# RS232_M_V1.net
KiCad netlist of a schematic drawn in Altium Designer
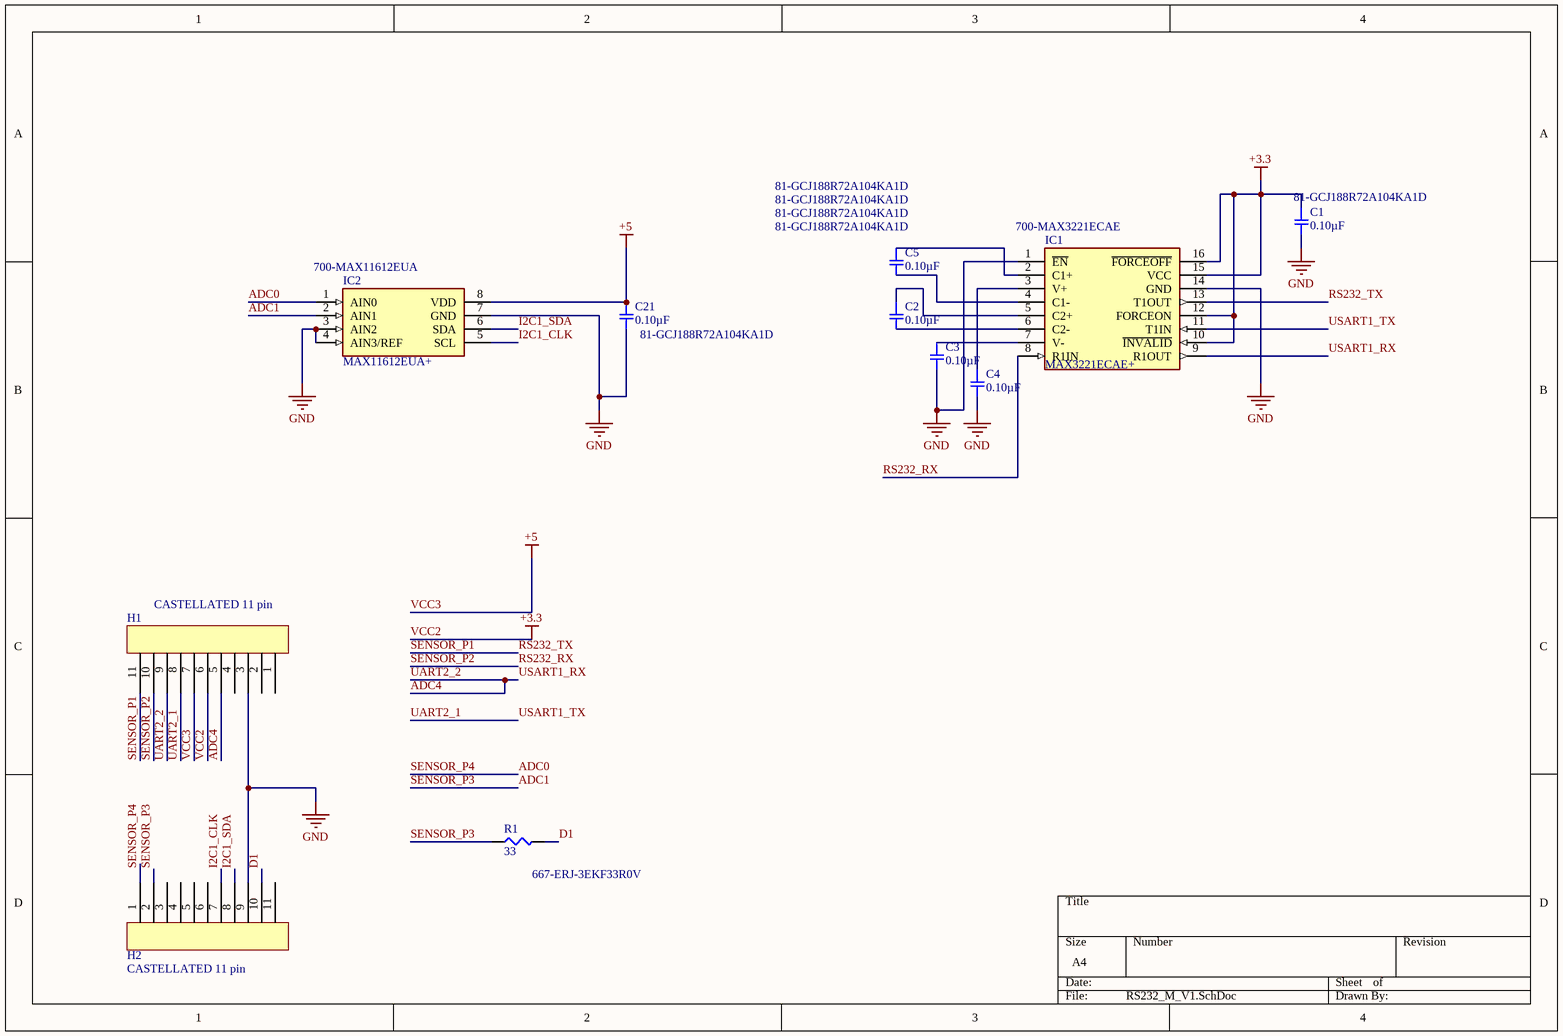
[diagram p0: RS232_M_V1.SchDoc]

(export (version "E")
  (design (tool "Eeschema 10.0.6"))
  (components
    (comp (ref "C1")
      (value "0.10µF")
      (footprint "SMD-0603C")
      (description "CAP CER 0.1UF 100V X7R 0603")
      (fields
        (field (name "PART NUMBER") "GCJ188R72A104KA01D")
        (field (name "DIGI-KEY PART NUMBER") "490-13420-1-ND")
        (field (name "SUPPLIER PART NUMBER 1") "81-GCJ188R72A104KA1D")
      )
      (libsource (lib "cap_murata") (part "CAPACITOR"))
    )
    (comp (ref "C2")
      (value "0.10µF")
      (footprint "SMD-0603C")
      (description "CAP CER 0.1UF 100V X7R 0603")
      (fields
        (field (name "PART NUMBER") "GCJ188R72A104KA01D")
        (field (name "DIGI-KEY PART NUMBER") "490-13420-1-ND")
        (field (name "SUPPLIER PART NUMBER 1") "81-GCJ188R72A104KA1D")
      )
      (libsource (lib "cap_murata") (part "CAPACITOR"))
    )
    (comp (ref "C3")
      (value "0.10µF")
      (footprint "SMD-0603C")
      (description "CAP CER 0.1UF 100V X7R 0603")
      (fields
        (field (name "PART NUMBER") "GCJ188R72A104KA01D")
        (field (name "DIGI-KEY PART NUMBER") "490-13420-1-ND")
        (field (name "SUPPLIER PART NUMBER 1") "81-GCJ188R72A104KA1D")
      )
      (libsource (lib "cap_murata") (part "CAPACITOR"))
    )
    (comp (ref "C4")
      (value "0.10µF")
      (footprint "SMD-0603C")
      (description "CAP CER 0.1UF 100V X7R 0603")
      (fields
        (field (name "PART NUMBER") "GCJ188R72A104KA01D")
        (field (name "DIGI-KEY PART NUMBER") "490-13420-1-ND")
        (field (name "SUPPLIER PART NUMBER 1") "81-GCJ188R72A104KA1D")
      )
      (libsource (lib "cap_murata") (part "CAPACITOR"))
    )
    (comp (ref "C5")
      (value "0.10µF")
      (footprint "SMD-0603C")
      (description "CAP CER 0.1UF 100V X7R 0603")
      (fields
        (field (name "PART NUMBER") "GCJ188R72A104KA01D")
        (field (name "DIGI-KEY PART NUMBER") "490-13420-1-ND")
        (field (name "SUPPLIER PART NUMBER 1") "81-GCJ188R72A104KA1D")
      )
      (libsource (lib "cap_murata") (part "CAPACITOR"))
    )
    (comp (ref "C21")
      (value "0.10µF")
      (footprint "SMD-0603C")
      (description "CAP CER 0.1UF 100V X7R 0603")
      (fields
        (field (name "PART NUMBER") "GCJ188R72A104KA01D")
        (field (name "DIGI-KEY PART NUMBER") "490-13420-1-ND")
        (field (name "SUPPLIER PART NUMBER 1") "81-GCJ188R72A104KA1D")
      )
      (libsource (lib "cap_murata") (part "CAPACITOR"))
    )
    (comp (ref "H1")
      (value "CASTELLATED 11 pin")
      (footprint "CASTELLATED 11 pin")
      (libsource (lib "USIB") (part "CASTELLATED 11 pin"))
    )
    (comp (ref "H2")
      (value "CASTELLATED 11 pin")
      (footprint "CASTELLATED 11 pin")
      (libsource (lib "") (part "CASTELLATED 11 pin_1"))
    )
    (comp (ref "IC1")
      (value "MAX3221ECAE+")
      (footprint "SamacSys:SOP65P778X199-16N")
      (description "Integrated Circuit")
      (fields (field (name "SUPPLIER PART NUMBER 1") "700-MAX3221ECAE"))
      (libsource (lib "*") (part "MAX3221ECAE+"))
    )
    (comp (ref "IC2")
      (value "MAX11612EUA+")
      (footprint "SOP65P490X110-8N")
      (description "Integrated Circuit")
      (fields (field (name "SUPPLIER PART NUMBER 1") "700-MAX11612EUA"))
      (libsource (lib "SamacSys") (part "MAX11612EUA+"))
    )
    (comp (ref "R1")
      (value "33")
      (footprint "SMD-0603-RES")
      (description "RES SMD 33 OHM 1% 1/10W 0603")
      (fields
        (field (name "PART NUMBER") "ERJ-3EKF33R0V")
        (field (name "DIGI-KEY PART NUMBER") "P33.0HCT-ND")
        (field (name "SUPPLIER PART NUMBER 1") "667-ERJ-3EKF33R0V")
      )
      (libsource (lib "Panasonic_ERJ_0603") (part "ERJ-3EKF33R0V"))
    )
  )
  (nets
    (net (code "1") (name "+3.3") (class "Default")
      (node (ref "C1") (pin "1") (pinfunction "1_1") (pintype "passive"))
      (node (ref "H1") (pin "6") (pintype "passive"))
      (node (ref "IC1") (pin "10") (pinfunction "~{INVALID}_10") (pintype "input"))
      (node (ref "IC1") (pin "12") (pinfunction "FORCEON_12") (pintype "passive"))
      (node (ref "IC1") (pin "15") (pinfunction "VCC_15") (pintype "power_in"))
      (node (ref "IC1") (pin "16") (pinfunction "~{FORCEOFF}_16") (pintype "passive"))
    )
    (net (code "2") (name "+5") (class "Default")
      (node (ref "C21") (pin "1") (pinfunction "1_1") (pintype "passive"))
      (node (ref "H1") (pin "7") (pintype "passive"))
      (node (ref "IC2") (pin "8") (pinfunction "VDD_8") (pintype "power_in"))
    )
    (net (code "3") (name "/ADC0") (class "Default")
      (node (ref "H2") (pin "1") (pintype "passive"))
      (node (ref "IC2") (pin "1") (pinfunction "AIN0_1") (pintype "input"))
    )
    (net (code "4") (name "/ADC1") (class "Default")
      (node (ref "H2") (pin "2") (pintype "passive"))
      (node (ref "IC2") (pin "2") (pinfunction "AIN1_2") (pintype "input"))
      (node (ref "R1") (pin "1") (pinfunction "1_1") (pintype "passive"))
    )
    (net (code "5") (name "/ADC4") (class "Default")
      (node (ref "H1") (pin "5") (pintype "passive"))
      (node (ref "H1") (pin "9") (pintype "passive"))
      (node (ref "IC1") (pin "9") (pinfunction "R1OUT_9") (pintype "output"))
    )
    (net (code "6") (name "/D1") (class "Default")
      (node (ref "H2") (pin "10") (pintype "passive"))
      (node (ref "R1") (pin "2") (pinfunction "2_2") (pintype "passive"))
    )
    (net (code "7") (name "/I2C1_CLK") (class "Default")
      (node (ref "H2") (pin "7") (pintype "passive"))
      (node (ref "IC2") (pin "5") (pinfunction "SCL_5") (pintype "passive"))
    )
    (net (code "8") (name "/I2C1_SDA") (class "Default")
      (node (ref "H2") (pin "8") (pintype "passive"))
      (node (ref "IC2") (pin "6") (pinfunction "SDA_6") (pintype "passive"))
    )
    (net (code "9") (name "/RS232_RX") (class "Default")
      (node (ref "H1") (pin "10") (pintype "passive"))
      (node (ref "IC1") (pin "8") (pinfunction "R1IN_8") (pintype "input"))
    )
    (net (code "10") (name "/RS232_TX") (class "Default")
      (node (ref "H1") (pin "11") (pintype "passive"))
      (node (ref "IC1") (pin "13") (pinfunction "T1OUT_13") (pintype "output"))
    )
    (net (code "11") (name "/UART2_1") (class "Default")
      (node (ref "H1") (pin "8") (pintype "passive"))
      (node (ref "IC1") (pin "11") (pinfunction "T1IN_11") (pintype "input"))
    )
    (net (code "12") (name "GND") (class "Default")
      (node (ref "C1") (pin "2") (pinfunction "2_2") (pintype "passive"))
      (node (ref "C21") (pin "2") (pinfunction "2_2") (pintype "passive"))
      (node (ref "C3") (pin "2") (pinfunction "2_2") (pintype "passive"))
      (node (ref "C4") (pin "2") (pinfunction "2_2") (pintype "passive"))
      (node (ref "H1") (pin "3") (pintype "passive"))
      (node (ref "H2") (pin "9") (pintype "passive"))
      (node (ref "IC1") (pin "1") (pinfunction "~{EN}_1") (pintype "passive"))
      (node (ref "IC1") (pin "14") (pinfunction "GND_14") (pintype "power_in"))
      (node (ref "IC2") (pin "3") (pinfunction "AIN2_3") (pintype "input"))
      (node (ref "IC2") (pin "4") (pinfunction "AIN3/REF_4") (pintype "input"))
      (node (ref "IC2") (pin "7") (pinfunction "GND_7") (pintype "power_in"))
    )
    (net (code "13") (name "Net-(IC1-C1+)") (class "Default")
      (node (ref "C5") (pin "1") (pinfunction "1_1") (pintype "passive"))
      (node (ref "IC1") (pin "2") (pinfunction "C1+_2") (pintype "passive"))
    )
    (net (code "14") (name "Net-(IC1-C1-)") (class "Default")
      (node (ref "C5") (pin "2") (pinfunction "2_2") (pintype "passive"))
      (node (ref "IC1") (pin "4") (pinfunction "C1-_4") (pintype "passive"))
    )
    (net (code "15") (name "Net-(IC1-C2+)") (class "Default")
      (node (ref "C2") (pin "1") (pinfunction "1_1") (pintype "passive"))
      (node (ref "IC1") (pin "5") (pinfunction "C2+_5") (pintype "passive"))
    )
    (net (code "16") (name "Net-(IC1-C2-)") (class "Default")
      (node (ref "C2") (pin "2") (pinfunction "2_2") (pintype "passive"))
      (node (ref "IC1") (pin "6") (pinfunction "C2-_6") (pintype "passive"))
    )
    (net (code "17") (name "Net-(IC1-V+)") (class "Default")
      (node (ref "C4") (pin "1") (pinfunction "1_1") (pintype "passive"))
      (node (ref "IC1") (pin "3") (pinfunction "V+_3") (pintype "passive"))
    )
    (net (code "18") (name "Net-(IC1-V-)") (class "Default")
      (node (ref "C3") (pin "1") (pinfunction "1_1") (pintype "passive"))
      (node (ref "IC1") (pin "7") (pinfunction "V-_7") (pintype "passive"))
    )
    (net (code "19") (name "unconnected-(H1-Pad1)") (class "Default")
      (node (ref "H1") (pin "1") (pintype "passive"))
    )
    (net (code "20") (name "unconnected-(H1-Pad2)") (class "Default")
      (node (ref "H1") (pin "2") (pintype "passive"))
    )
    (net (code "21") (name "unconnected-(H1-Pad4)") (class "Default")
      (node (ref "H1") (pin "4") (pintype "passive"))
    )
    (net (code "22") (name "unconnected-(H2-Pad3)") (class "Default")
      (node (ref "H2") (pin "3") (pintype "passive"))
    )
    (net (code "23") (name "unconnected-(H2-Pad4)") (class "Default")
      (node (ref "H2") (pin "4") (pintype "passive"))
    )
    (net (code "24") (name "unconnected-(H2-Pad5)") (class "Default")
      (node (ref "H2") (pin "5") (pintype "passive"))
    )
    (net (code "25") (name "unconnected-(H2-Pad6)") (class "Default")
      (node (ref "H2") (pin "6") (pintype "passive"))
    )
    (net (code "26") (name "unconnected-(H2-Pad11)") (class "Default")
      (node (ref "H2") (pin "11") (pintype "passive"))
    )
  )
)
